# VW.net
KiCad netlist of a schematic drawn in EAGLE
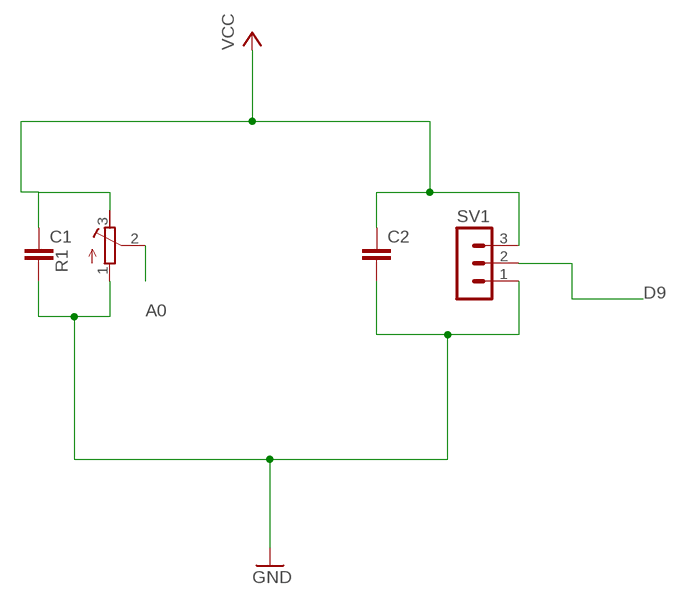
[diagram p0: schematic, sheet 1]

(export (version "E")
  (design (tool "Eeschema 10.0.6"))
  (components
    (comp (ref "C1")
      (value "C2,5-3")
      (footprint "eagle-import:C2.5-3")
      (libsource (lib "eagle-import") (part "C2,5-3"))
    )
    (comp (ref "C2")
      (value "C2,5-3")
      (footprint "eagle-import:C2.5-3")
      (libsource (lib "eagle-import") (part "C2,5-3"))
    )
    (comp (ref "R1")
      (value "R-TRIMM4G/J")
      (footprint "eagle-import:RTRIM4G_J")
      (libsource (lib "eagle-import") (part "R-TRIMM4G/J"))
    )
    (comp (ref "SV1")
      (value "MA03-1")
      (footprint "eagle-import:MA03-1")
      (libsource (lib "eagle-import") (part "MA03-1"))
    )
  )
  (nets
    (net (code "1") (name "/A0") (class "Default")
      (node (ref "R1") (pin "2") (pinfunction "S_2") (pintype "passive"))
    )
    (net (code "2") (name "/D9") (class "Default")
      (node (ref "SV1") (pin "2") (pinfunction "2_2") (pintype "passive"))
    )
    (net (code "3") (name "GND") (class "Default")
      (node (ref "C1") (pin "2") (pinfunction "2_2") (pintype "passive"))
      (node (ref "C2") (pin "2") (pinfunction "2_2") (pintype "passive"))
      (node (ref "R1") (pin "1") (pinfunction "A_1") (pintype "passive"))
      (node (ref "SV1") (pin "1") (pinfunction "1_1") (pintype "passive"))
    )
    (net (code "4") (name "VCC") (class "Default")
      (node (ref "C1") (pin "1") (pinfunction "1_1") (pintype "passive"))
      (node (ref "C2") (pin "1") (pinfunction "1_1") (pintype "passive"))
      (node (ref "R1") (pin "3") (pinfunction "E_3") (pintype "passive"))
      (node (ref "SV1") (pin "3") (pinfunction "3_3") (pintype "passive"))
    )
  )
)
